# RS232.net
KiCad netlist of a schematic drawn in Altium Designer
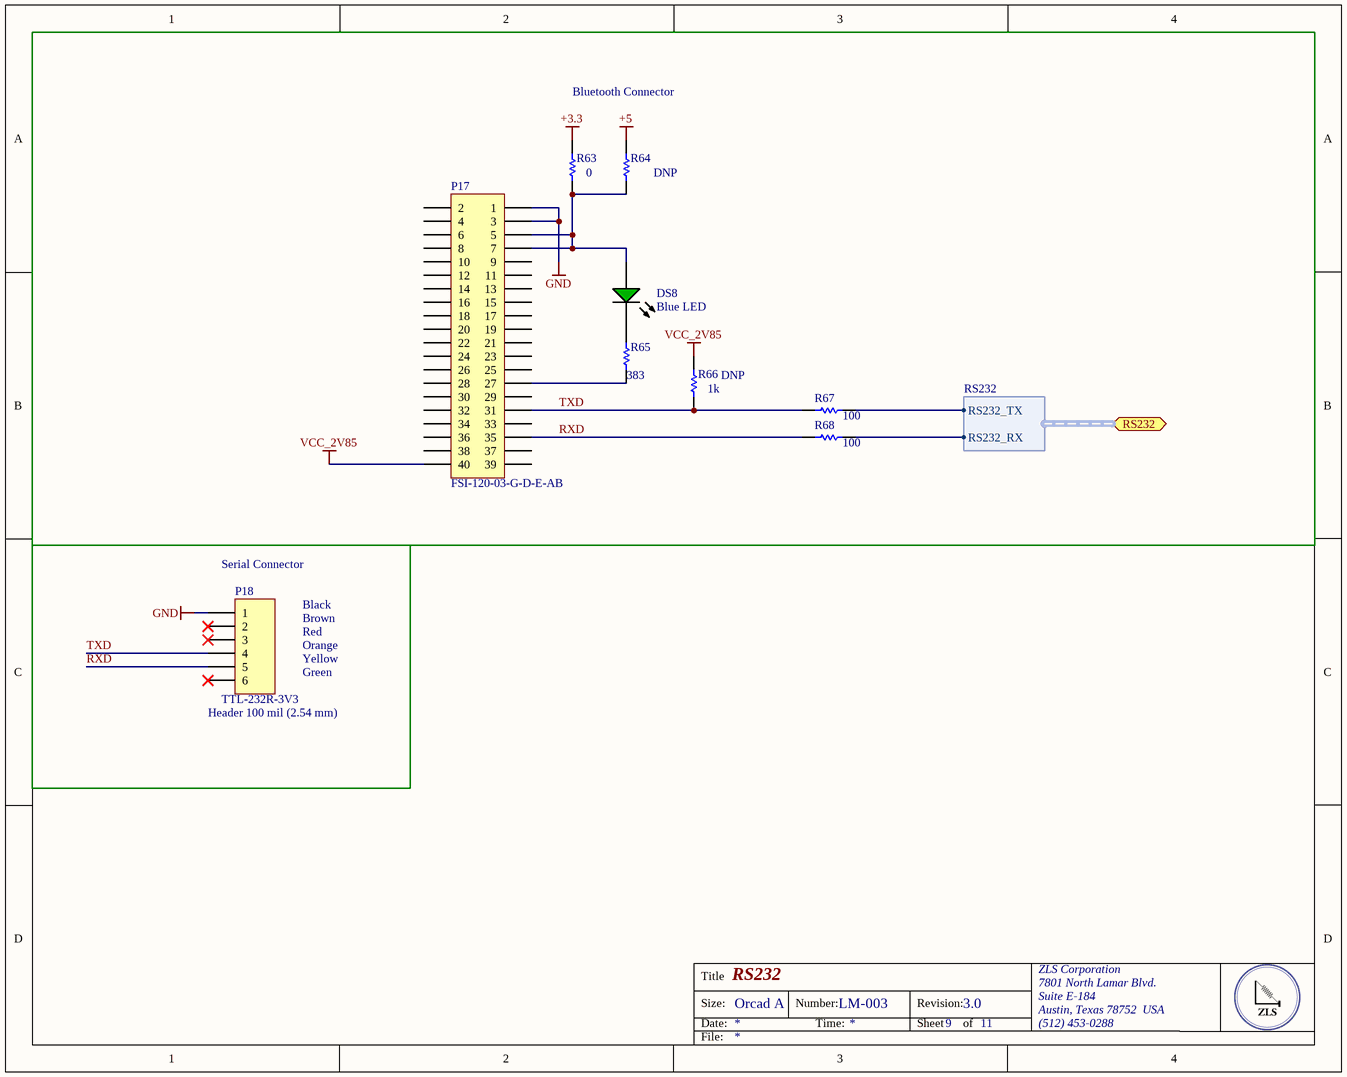
[diagram p0: RS232.SchDoc]

(export (version "E")
  (design (tool "Eeschema 10.0.6"))
  (components
    (comp (ref "DS8")
      (value "Blue LED")
      (footprint "KING-LED0603-25-GREEN_V")
      (description "LED 468NM BLUE CLEAR 0603 SMD")
      (libsource (lib "Altium Content Vault") (part "CMP-0239-00001-1"))
    )
    (comp (ref "P17")
      (value "FSI-120-03-G-D-E-AB")
      (footprint "FSI-120-03-G-D-E-AB")
      (description "1MM SINGLE ELEMENT INTERFACE")
      (libsource (lib "Miscellaneous Connectors") (part "Header 20X2"))
    )
    (comp (ref "P18")
      (value "Header 100 mil (2.54 mm)")
      (footprint "HDR1X6")
      (description "CABLE USB SERIAL 3.3V 2MM HEADER")
      (libsource (lib "Miscellaneous Connectors") (part "Header 6H"))
    )
    (comp (ref "R63")
      (value "RES SMD 0.0 OHM JUMPER 1/8W 0805")
      (footprint "RESC0805(2012)_M")
      (fields
        (field (name "MANUFACTURER") "Vishay")
        (field (name "MANUFACTURER PART NUMBER") "CRCW08050000Z0EA")
        (field (name "RESISTANCE") "0")
        (field (name "TOLERANCE") "1%")
      )
      (libsource (lib "Altium Content Vault") (part "CMP-1013-00017-1"))
    )
    (comp (ref "R64")
      (value "DNP")
      (footprint "RESC0805(2012)_M")
      (description "RES SMD 0.0 OHM JUMPER 1/8W 0805")
      (fields
        (field (name "MANUFACTURER") "Vishay")
        (field (name "MANUFACTURER PART NUMBER") "CRCW08050000Z0EA")
      )
      (libsource (lib "Altium Content Vault") (part "CMP-1013-00017-1"))
    )
    (comp (ref "R65")
      (value "RES SMD 383 OHM 1% 1/8W 0805")
      (footprint "RESC0805(2012)_M")
      (fields
        (field (name "MANUFACTURER") "Vishay Dale")
        (field (name "MANUFACTURER PART NUMBER") "CRCW0805383RFKEA")
        (field (name "RESISTANCE (OHMS)") "383")
        (field (name "TOLERANCE") "±1%")
      )
      (libsource (lib "Altium Content Vault") (part "CMP-1013-00017-1"))
    )
    (comp (ref "R66")
      (value "DNP")
      (footprint "RESC0805(2012)_M")
      (description "RES SMD 1K OHM 1% 1/2W 0805")
      (fields
        (field (name "MANUFACTURER") "Vishay Dale")
        (field (name "MANUFACTURER PART NUMBER") "CRCW08051K00FKEAHP")
        (field (name "RESISTANCE (OHMS)") "1k")
      )
      (libsource (lib "Altium Content Vault") (part "CMP-1013-00017-1"))
    )
    (comp (ref "R67")
      (value "RES SMD 100 OHM 1% 1/8W 0805")
      (footprint "RESC0805(2012)_L")
      (fields
        (field (name "MANUFACTURER") "Vishay Dale")
        (field (name "MANUFACTURER PART NUMBER") "CRCW0805100RFKEA")
        (field (name "RESISTANCE (OHMS)") "100")
        (field (name "TOLERANCE") "±1%")
      )
      (libsource (lib "Altium Content Vault") (part "CMP-1013-00393-1"))
    )
    (comp (ref "R68")
      (value "RES SMD 100 OHM 1% 1/8W 0805")
      (footprint "RESC0805(2012)_N")
      (fields
        (field (name "MANUFACTURER") "Vishay Dale")
        (field (name "MANUFACTURER PART NUMBER") "CRCW0805100RFKEA")
        (field (name "RESISTANCE (OHMS)") "100")
        (field (name "TOLERANCE") "±1%")
      )
      (libsource (lib "Altium Content Vault") (part "CMP-1013-00393-1"))
    )
  )
  (nets
    (net (code "2") (name "+3.3") (class "Default")
      (node (ref "R63") (pin "2") (pinfunction "2_2") (pintype "passive"))
    )
    (net (code "3") (name "+5") (class "Default")
      (node (ref "R64") (pin "2") (pinfunction "2_2") (pintype "passive"))
    )
    (net (code "4") (name "/RS232_RX") (class "Default")
      (node (ref "R68") (pin "1") (pinfunction "1_1") (pintype "passive"))
    )
    (net (code "5") (name "/RS232_TX") (class "Default")
      (node (ref "R67") (pin "1") (pinfunction "1_1") (pintype "passive"))
    )
    (net (code "6") (name "/RXD") (class "Default")
      (node (ref "P17") (pin "35") (pinfunction "35_35") (pintype "passive"))
      (node (ref "P18") (pin "5") (pinfunction "5_5") (pintype "passive"))
      (node (ref "R68") (pin "2") (pinfunction "2_2") (pintype "passive"))
    )
    (net (code "7") (name "/TXD") (class "Default")
      (node (ref "P17") (pin "31") (pinfunction "31_31") (pintype "passive"))
      (node (ref "P18") (pin "4") (pinfunction "4_4") (pintype "passive"))
      (node (ref "R66") (pin "1") (pinfunction "1_1") (pintype "passive"))
      (node (ref "R67") (pin "2") (pinfunction "2_2") (pintype "passive"))
    )
    (net (code "9") (name "GND") (class "Default")
      (node (ref "P17") (pin "1") (pinfunction "1_1") (pintype "passive"))
      (node (ref "P17") (pin "3") (pinfunction "3_3") (pintype "passive"))
      (node (ref "P18") (pin "1") (pinfunction "1_1") (pintype "passive"))
    )
    (net (code "10") (name "Net-(DS8-A)") (class "Default")
      (node (ref "DS8") (pin "1") (pinfunction "A_1") (pintype "passive"))
      (node (ref "P17") (pin "5") (pinfunction "5_5") (pintype "passive"))
      (node (ref "P17") (pin "7") (pinfunction "7_7") (pintype "passive"))
      (node (ref "R63") (pin "1") (pinfunction "1_1") (pintype "passive"))
      (node (ref "R64") (pin "1") (pinfunction "1_1") (pintype "passive"))
    )
    (net (code "11") (name "Net-(DS8-K)") (class "Default")
      (node (ref "DS8") (pin "2") (pinfunction "K_2") (pintype "passive"))
      (node (ref "R65") (pin "2") (pinfunction "2_2") (pintype "passive"))
    )
    (net (code "12") (name "Net-(P17-Pad27)") (class "Default")
      (node (ref "P17") (pin "27") (pinfunction "27_27") (pintype "passive"))
      (node (ref "R65") (pin "1") (pinfunction "1_1") (pintype "passive"))
    )
    (net (code "13") (name "VCC_2V85") (class "Default")
      (node (ref "P17") (pin "40") (pinfunction "40_40") (pintype "passive"))
      (node (ref "R66") (pin "2") (pinfunction "2_2") (pintype "passive"))
    )
    (net (code "14") (name "unconnected-(P17-Pad2)") (class "Default")
      (node (ref "P17") (pin "2") (pinfunction "2_2") (pintype "passive"))
    )
    (net (code "15") (name "unconnected-(P17-Pad4)") (class "Default")
      (node (ref "P17") (pin "4") (pinfunction "4_4") (pintype "passive"))
    )
    (net (code "16") (name "unconnected-(P17-Pad6)") (class "Default")
      (node (ref "P17") (pin "6") (pinfunction "6_6") (pintype "passive"))
    )
    (net (code "17") (name "unconnected-(P17-Pad8)") (class "Default")
      (node (ref "P17") (pin "8") (pinfunction "8_8") (pintype "passive"))
    )
    (net (code "18") (name "unconnected-(P17-Pad9)") (class "Default")
      (node (ref "P17") (pin "9") (pinfunction "9_9") (pintype "passive"))
    )
    (net (code "19") (name "unconnected-(P17-Pad10)") (class "Default")
      (node (ref "P17") (pin "10") (pinfunction "10_10") (pintype "passive"))
    )
    (net (code "20") (name "unconnected-(P17-Pad11)") (class "Default")
      (node (ref "P17") (pin "11") (pinfunction "11_11") (pintype "passive"))
    )
    (net (code "21") (name "unconnected-(P17-Pad12)") (class "Default")
      (node (ref "P17") (pin "12") (pinfunction "12_12") (pintype "passive"))
    )
    (net (code "22") (name "unconnected-(P17-Pad13)") (class "Default")
      (node (ref "P17") (pin "13") (pinfunction "13_13") (pintype "passive"))
    )
    (net (code "23") (name "unconnected-(P17-Pad14)") (class "Default")
      (node (ref "P17") (pin "14") (pinfunction "14_14") (pintype "passive"))
    )
    (net (code "24") (name "unconnected-(P17-Pad15)") (class "Default")
      (node (ref "P17") (pin "15") (pinfunction "15_15") (pintype "passive"))
    )
    (net (code "25") (name "unconnected-(P17-Pad16)") (class "Default")
      (node (ref "P17") (pin "16") (pinfunction "16_16") (pintype "passive"))
    )
    (net (code "26") (name "unconnected-(P17-Pad17)") (class "Default")
      (node (ref "P17") (pin "17") (pinfunction "17_17") (pintype "passive"))
    )
    (net (code "27") (name "unconnected-(P17-Pad18)") (class "Default")
      (node (ref "P17") (pin "18") (pinfunction "18_18") (pintype "passive"))
    )
    (net (code "28") (name "unconnected-(P17-Pad19)") (class "Default")
      (node (ref "P17") (pin "19") (pinfunction "19_19") (pintype "passive"))
    )
    (net (code "29") (name "unconnected-(P17-Pad20)") (class "Default")
      (node (ref "P17") (pin "20") (pinfunction "20_20") (pintype "passive"))
    )
    (net (code "30") (name "unconnected-(P17-Pad21)") (class "Default")
      (node (ref "P17") (pin "21") (pinfunction "21_21") (pintype "passive"))
    )
    (net (code "31") (name "unconnected-(P17-Pad22)") (class "Default")
      (node (ref "P17") (pin "22") (pinfunction "22_22") (pintype "passive"))
    )
    (net (code "32") (name "unconnected-(P17-Pad23)") (class "Default")
      (node (ref "P17") (pin "23") (pinfunction "23_23") (pintype "passive"))
    )
    (net (code "33") (name "unconnected-(P17-Pad24)") (class "Default")
      (node (ref "P17") (pin "24") (pinfunction "24_24") (pintype "passive"))
    )
    (net (code "34") (name "unconnected-(P17-Pad25)") (class "Default")
      (node (ref "P17") (pin "25") (pinfunction "25_25") (pintype "passive"))
    )
    (net (code "35") (name "unconnected-(P17-Pad26)") (class "Default")
      (node (ref "P17") (pin "26") (pinfunction "26_26") (pintype "passive"))
    )
    (net (code "36") (name "unconnected-(P17-Pad28)") (class "Default")
      (node (ref "P17") (pin "28") (pinfunction "28_28") (pintype "passive"))
    )
    (net (code "37") (name "unconnected-(P17-Pad29)") (class "Default")
      (node (ref "P17") (pin "29") (pinfunction "29_29") (pintype "passive"))
    )
    (net (code "38") (name "unconnected-(P17-Pad30)") (class "Default")
      (node (ref "P17") (pin "30") (pinfunction "30_30") (pintype "passive"))
    )
    (net (code "39") (name "unconnected-(P17-Pad32)") (class "Default")
      (node (ref "P17") (pin "32") (pinfunction "32_32") (pintype "passive"))
    )
    (net (code "40") (name "unconnected-(P17-Pad33)") (class "Default")
      (node (ref "P17") (pin "33") (pinfunction "33_33") (pintype "passive"))
    )
    (net (code "41") (name "unconnected-(P17-Pad34)") (class "Default")
      (node (ref "P17") (pin "34") (pinfunction "34_34") (pintype "passive"))
    )
    (net (code "42") (name "unconnected-(P17-Pad36)") (class "Default")
      (node (ref "P17") (pin "36") (pinfunction "36_36") (pintype "passive"))
    )
    (net (code "43") (name "unconnected-(P17-Pad37)") (class "Default")
      (node (ref "P17") (pin "37") (pinfunction "37_37") (pintype "passive"))
    )
    (net (code "44") (name "unconnected-(P17-Pad38)") (class "Default")
      (node (ref "P17") (pin "38") (pinfunction "38_38") (pintype "passive"))
    )
    (net (code "45") (name "unconnected-(P17-Pad39)") (class "Default")
      (node (ref "P17") (pin "39") (pinfunction "39_39") (pintype "passive"))
    )
    (net (code "46") (name "unconnected-(P18-Pad2)") (class "Default")
      (node (ref "P18") (pin "2") (pinfunction "2_2") (pintype "passive+no_connect"))
    )
    (net (code "47") (name "unconnected-(P18-Pad3)") (class "Default")
      (node (ref "P18") (pin "3") (pinfunction "3_3") (pintype "passive+no_connect"))
    )
    (net (code "48") (name "unconnected-(P18-Pad6)") (class "Default")
      (node (ref "P18") (pin "6") (pinfunction "6_6") (pintype "passive+no_connect"))
    )
  )
)
